# IoT_modules_atmega328_kinemata_v1.net
KiCad netlist of a schematic drawn in EAGLE
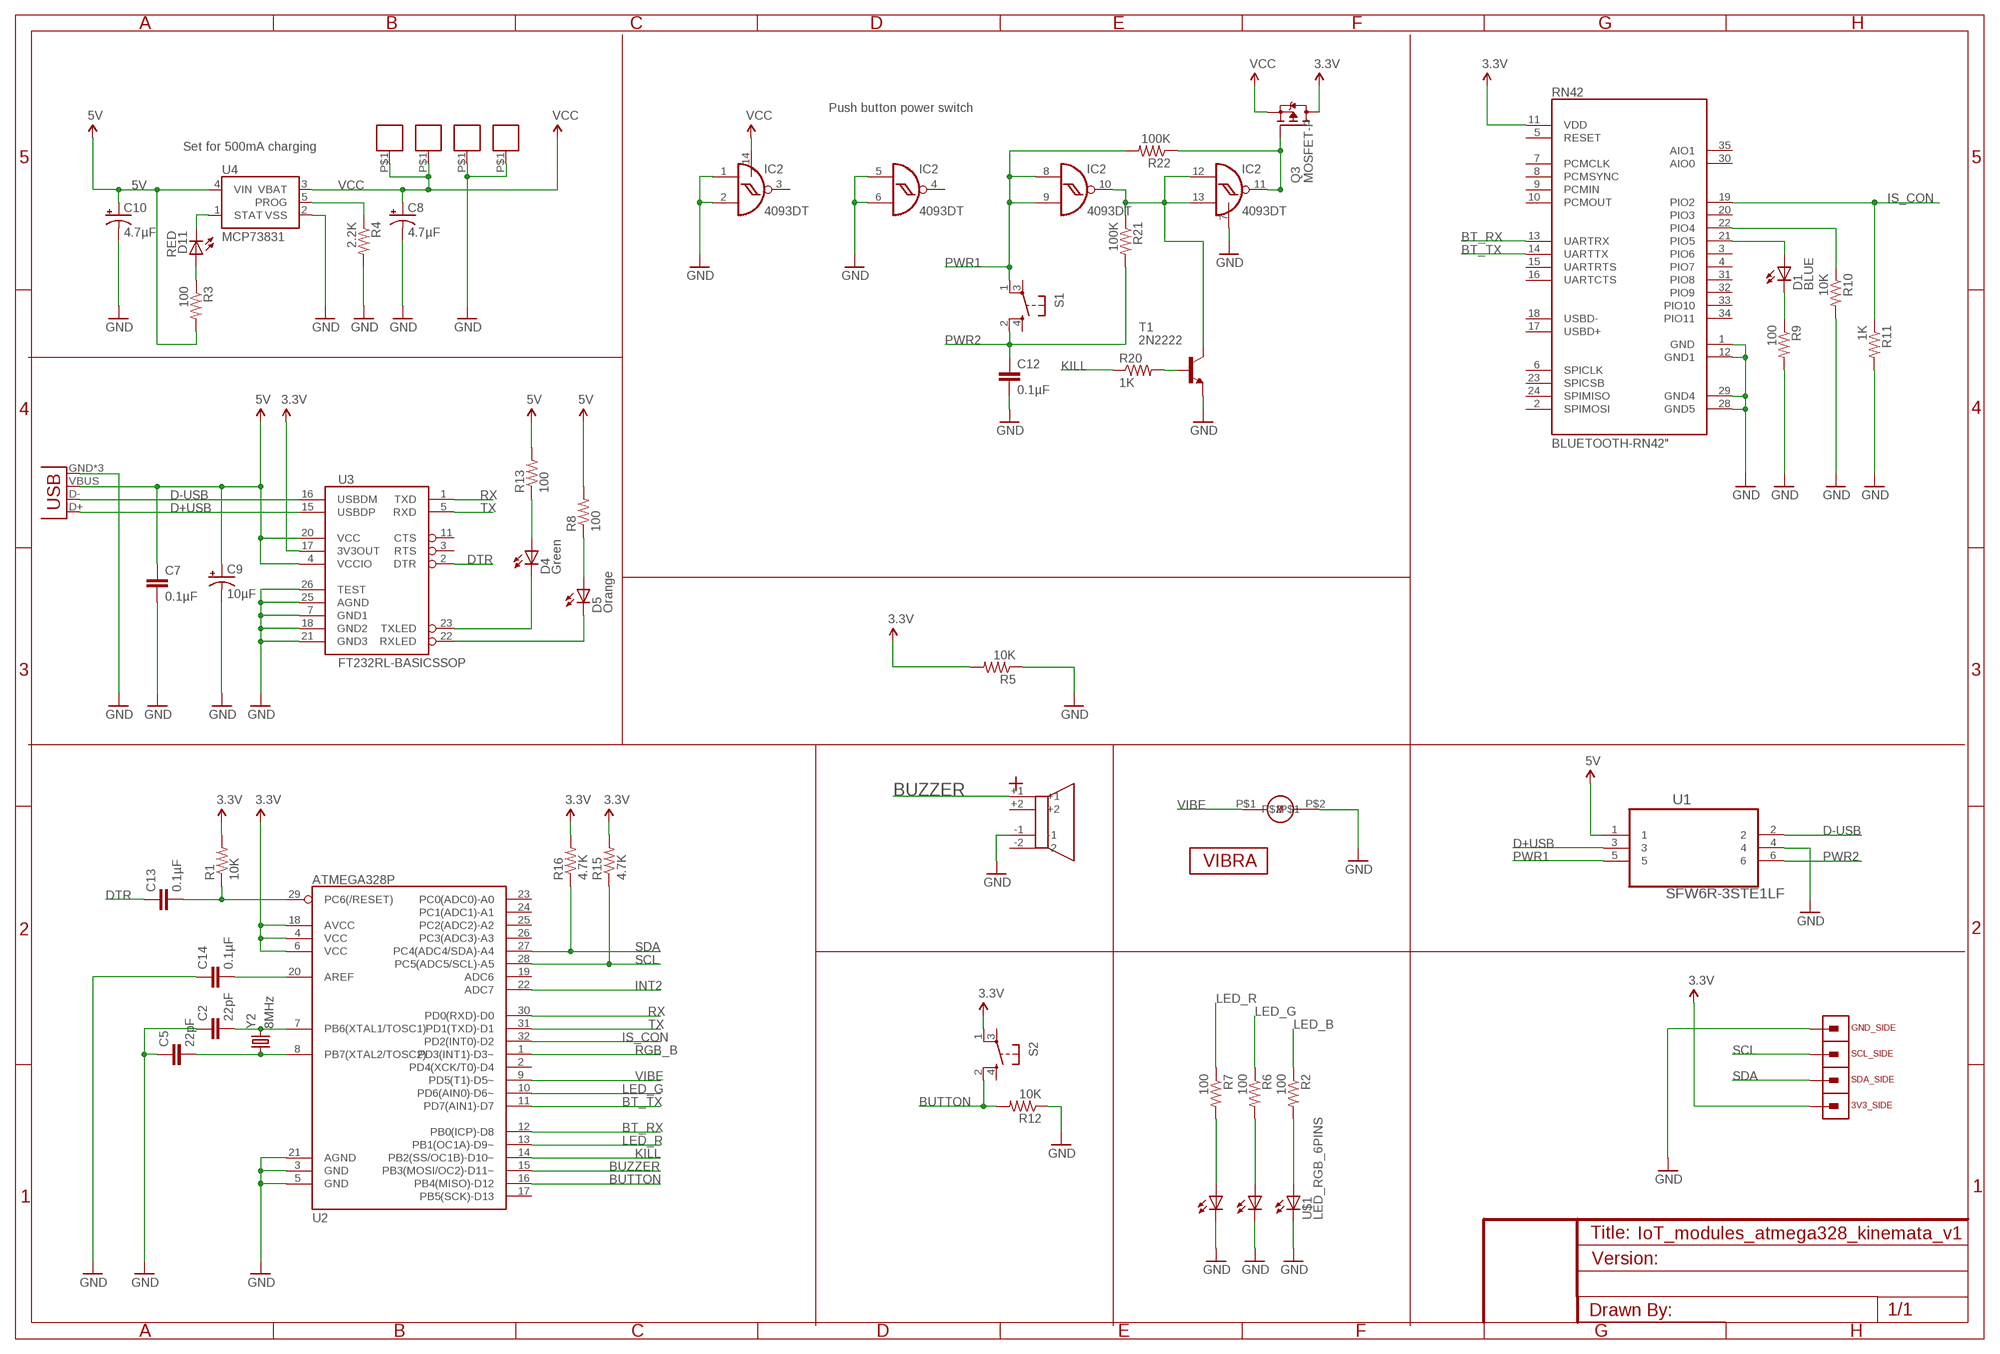
[diagram p0: schematic, sheet 1]

(export (version "E")
  (design (tool "Eeschema 10.0.6"))
  (components
    (comp (ref "3V3_SIDE")
      (value "HEADER_1PIN_MALE")
      (footprint "eagle-import:SPRING_LOADED_HEADER_ANGLE_829-22-020-20-002101_DIGIKEY_ED1320-ND")
      (libsource (lib "eagle-import") (part "HEADER_1PIN_MALE"))
    )
    (comp (ref "BAT+1")
      (value "LIPO_PAD")
      (footprint "eagle-import:LIPO_PAD")
      (libsource (lib "eagle-import") (part "LIPO_PAD"))
    )
    (comp (ref "BAT+2")
      (value "LIPO_PAD")
      (footprint "eagle-import:LIPO_PAD")
      (libsource (lib "eagle-import") (part "LIPO_PAD"))
    )
    (comp (ref "BAT-1")
      (value "LIPO_PAD")
      (footprint "eagle-import:LIPO_PAD")
      (libsource (lib "eagle-import") (part "LIPO_PAD"))
    )
    (comp (ref "BAT-2")
      (value "LIPO_PAD")
      (footprint "eagle-import:LIPO_PAD")
      (libsource (lib "eagle-import") (part "LIPO_PAD"))
    )
    (comp (ref "C2")
      (value "22pF")
      (footprint "eagle-import:1206")
      (libsource (lib "eagle-import") (part "CAP1206"))
    )
    (comp (ref "C5")
      (value "22pF")
      (footprint "eagle-import:1206")
      (libsource (lib "eagle-import") (part "CAP1206"))
    )
    (comp (ref "C7")
      (value "0.1µF")
      (footprint "eagle-import:1206")
      (libsource (lib "eagle-import") (part "CAP1206"))
    )
    (comp (ref "C8")
      (value "4.7µF")
      (footprint "eagle-import:EIA3216")
      (libsource (lib "eagle-import") (part "CAP_POL1206"))
    )
    (comp (ref "C9")
      (value "10µF")
      (footprint "eagle-import:EIA3216")
      (libsource (lib "eagle-import") (part "CAP_POL1206"))
    )
    (comp (ref "C10")
      (value "4.7µF")
      (footprint "eagle-import:EIA3216")
      (libsource (lib "eagle-import") (part "CAP_POL1206"))
    )
    (comp (ref "C12")
      (value "0.1µF")
      (footprint "eagle-import:1206")
      (libsource (lib "eagle-import") (part "CAP1206"))
    )
    (comp (ref "C13")
      (value "0.1µF")
      (footprint "eagle-import:1206")
      (libsource (lib "eagle-import") (part "CAP1206"))
    )
    (comp (ref "C14")
      (value "0.1µF")
      (footprint "eagle-import:1206")
      (libsource (lib "eagle-import") (part "CAP1206"))
    )
    (comp (ref "D1")
      (value "BLUE")
      (footprint "eagle-import:LED-1206")
      (libsource (lib "eagle-import") (part "LED1206"))
    )
    (comp (ref "D4")
      (value "Green")
      (footprint "eagle-import:LED-1206")
      (libsource (lib "eagle-import") (part "LED1206"))
    )
    (comp (ref "D5")
      (value "Orange")
      (footprint "eagle-import:LED-1206")
      (libsource (lib "eagle-import") (part "LED1206"))
    )
    (comp (ref "D11")
      (value "RED")
      (footprint "eagle-import:LED-1206")
      (libsource (lib "eagle-import") (part "LED1206"))
    )
    (comp (ref "GND_SIDE")
      (value "HEADER_1PIN_MALE")
      (footprint "eagle-import:SPRING_LOADED_HEADER_ANGLE_829-22-020-20-002101_DIGIKEY_ED1320-ND")
      (libsource (lib "eagle-import") (part "HEADER_1PIN_MALE"))
    )
    (comp (ref "IC2")
      (value "4093DT")
      (footprint "eagle-import:MC14093B-TSSOP14")
      (libsource (lib "eagle-import") (part "4093DT"))
    )
    (comp (ref "JP6")
      (value "USB-MICROB")
      (footprint "eagle-import:USB-MICROB")
      (libsource (lib "eagle-import") (part "USB-MICROB"))
    )
    (comp (ref "Q3")
      (value "MOSFET-P")
      (footprint "eagle-import:SOT23")
      (libsource (lib "eagle-import") (part "MOSFET-P"))
    )
    (comp (ref "R1")
      (value "10K")
      (footprint "eagle-import:1206")
      (libsource (lib "eagle-import") (part "RESISTOR1206"))
    )
    (comp (ref "R2")
      (value "100")
      (footprint "eagle-import:1206")
      (libsource (lib "eagle-import") (part "RESISTOR1206"))
    )
    (comp (ref "R3")
      (value "100")
      (footprint "eagle-import:1206")
      (libsource (lib "eagle-import") (part "RESISTOR1206"))
    )
    (comp (ref "R4")
      (value "2.2K")
      (footprint "eagle-import:1206")
      (libsource (lib "eagle-import") (part "RESISTOR1206"))
    )
    (comp (ref "R5")
      (value "10K")
      (footprint "eagle-import:1206")
      (libsource (lib "eagle-import") (part "RESISTOR1206"))
    )
    (comp (ref "R6")
      (value "100")
      (footprint "eagle-import:1206")
      (libsource (lib "eagle-import") (part "RESISTOR1206"))
    )
    (comp (ref "R7")
      (value "100")
      (footprint "eagle-import:1206")
      (libsource (lib "eagle-import") (part "RESISTOR1206"))
    )
    (comp (ref "R8")
      (value "100")
      (footprint "eagle-import:1206")
      (libsource (lib "eagle-import") (part "RESISTOR1206"))
    )
    (comp (ref "R9")
      (value "100")
      (footprint "eagle-import:1206")
      (libsource (lib "eagle-import") (part "RESISTOR1206"))
    )
    (comp (ref "R10")
      (value "10K")
      (footprint "eagle-import:1206")
      (libsource (lib "eagle-import") (part "RESISTOR1206"))
    )
    (comp (ref "R11")
      (value "1K")
      (footprint "eagle-import:1206")
      (libsource (lib "eagle-import") (part "RESISTOR1206"))
    )
    (comp (ref "R12")
      (value "10K")
      (footprint "eagle-import:1206")
      (libsource (lib "eagle-import") (part "RESISTOR1206"))
    )
    (comp (ref "R13")
      (value "100")
      (footprint "eagle-import:1206")
      (libsource (lib "eagle-import") (part "RESISTOR1206"))
    )
    (comp (ref "R15")
      (value "4.7K")
      (footprint "eagle-import:1206")
      (libsource (lib "eagle-import") (part "RESISTOR1206"))
    )
    (comp (ref "R16")
      (value "4.7K")
      (footprint "eagle-import:1206")
      (libsource (lib "eagle-import") (part "RESISTOR1206"))
    )
    (comp (ref "R20")
      (value "1K")
      (footprint "eagle-import:1206")
      (libsource (lib "eagle-import") (part "RESISTOR1206"))
    )
    (comp (ref "R21")
      (value "100K")
      (footprint "eagle-import:1206")
      (libsource (lib "eagle-import") (part "RESISTOR1206"))
    )
    (comp (ref "R22")
      (value "100K")
      (footprint "eagle-import:1206")
      (libsource (lib "eagle-import") (part "RESISTOR1206"))
    )
    (comp (ref "RN42")
      (value "BLUETOOTH-RN42\"")
      (footprint "eagle-import:RN42")
      (libsource (lib "eagle-import") (part "BLUETOOTH-RN42{dblquote}"))
    )
    (comp (ref "S1")
      (value "TAC_SWITCH_SIDEWAY")
      (footprint "eagle-import:TACTILE_SWITCH_ANGLE_SMD")
      (libsource (lib "eagle-import") (part "TAC_SWITCH_SIDEWAY"))
    )
    (comp (ref "S2")
      (value "TAC_SWITCH_SIDEWAY")
      (footprint "eagle-import:TACTILE_SWITCH_ANGLE_SMD")
      (libsource (lib "eagle-import") (part "TAC_SWITCH_SIDEWAY"))
    )
    (comp (ref "SCL_SIDE")
      (value "HEADER_1PIN_MALE")
      (footprint "eagle-import:SPRING_LOADED_HEADER_ANGLE_829-22-020-20-002101_DIGIKEY_ED1320-ND")
      (libsource (lib "eagle-import") (part "HEADER_1PIN_MALE"))
    )
    (comp (ref "SDA_SIDE")
      (value "HEADER_1PIN_MALE")
      (footprint "eagle-import:SPRING_LOADED_HEADER_ANGLE_829-22-020-20-002101_DIGIKEY_ED1320-ND")
      (libsource (lib "eagle-import") (part "HEADER_1PIN_MALE"))
    )
    (comp (ref "T1")
      (value "2N2222")
      (footprint "eagle-import:TO92-EBC-OVAL")
      (libsource (lib "eagle-import") (part "2N2222"))
    )
    (comp (ref "U$1")
      (value "LED_RGB_6PINS")
      (footprint "eagle-import:LED_RGB_6PINS")
      (libsource (lib "eagle-import") (part "LED_RGB_6PINS"))
    )
    (comp (ref "U$3")
      (value "BUZZER_4PINS")
      (footprint "eagle-import:FARNELL_BUZZER_MAGNETIC_SMD_3V_2215091")
      (libsource (lib "eagle-import") (part "BUZZER_4PINS"))
    )
    (comp (ref "U$4")
      (value "VIBRATION_MOTOR_SHAPE")
      (footprint "eagle-import:VIBRATION_MOTOR_SHAPE")
      (libsource (lib "eagle-import") (part "VIBRATION_MOTOR_SHAPE"))
    )
    (comp (ref "U$5")
      (value "VIBRATION_MOTOR")
      (footprint "eagle-import:VIBRATION_MOTOR_CABLE")
      (libsource (lib "eagle-import") (part "VIBRATION_MOTOR"))
    )
    (comp (ref "U1")
      (value "SFW6R-3STE1LF")
      (footprint "eagle-import:FCI_SFW6R-3STE1LF")
      (libsource (lib "eagle-import") (part "SFW6R-3STE1LF"))
    )
    (comp (ref "U2")
      (value "ATMEGA328P")
      (footprint "eagle-import:TQFP32-08")
      (libsource (lib "eagle-import") (part "ATMEGA328_SMT"))
    )
    (comp (ref "U3")
      (value "FT232RL-BASICSSOP")
      (footprint "eagle-import:SSOP28DB")
      (libsource (lib "eagle-import") (part "FT232RL-BASICSSOP"))
    )
    (comp (ref "U4")
      (value "MCP73831")
      (footprint "eagle-import:SOT23-5")
      (libsource (lib "eagle-import") (part "MCP73831"))
    )
    (comp (ref "Y2")
      (value "8MHz")
      (footprint "eagle-import:CRYSTAL_8MHZ_SMD_FARNELL_2101329")
      (libsource (lib "eagle-import") (part "CRYSTAL_2PINS5X3.2"))
    )
  )
  (nets
    (net (code "1") (name "/BT_RX") (class "Default")
      (node (ref "RN42") (pin "13") (pinfunction "UARTRX_13") (pintype "bidirectional"))
      (node (ref "U2") (pin "12") (pinfunction "PB0(ICP)-D8_12") (pintype "bidirectional"))
    )
    (net (code "2") (name "/BT_TX") (class "Default")
      (node (ref "RN42") (pin "14") (pinfunction "UARTTX_14") (pintype "bidirectional"))
      (node (ref "U2") (pin "11") (pinfunction "PD7(AIN1)-D7_11") (pintype "bidirectional"))
    )
    (net (code "3") (name "/BUTTON") (class "Default")
      (node (ref "R12") (pin "2") (pinfunction "2_2") (pintype "passive"))
      (node (ref "S2") (pin "2") (pinfunction "B2_2") (pintype "passive"))
      (node (ref "U2") (pin "16") (pinfunction "PB4(MISO)-D12_16") (pintype "bidirectional"))
    )
    (net (code "4") (name "/BUZZER") (class "Default")
      (node (ref "U$3") (pin "+1") (pinfunction "+1_+1") (pintype "bidirectional"))
      (node (ref "U2") (pin "15") (pinfunction "PB3(MOSI/OC2)-D11~{}_15") (pintype "bidirectional"))
    )
    (net (code "5") (name "/D+USB") (class "Default")
      (node (ref "JP6") (pin "D+") (pinfunction "D+_D+") (pintype "bidirectional"))
      (node (ref "U1") (pin "3") (pinfunction "3_3") (pintype "passive"))
      (node (ref "U3") (pin "15") (pinfunction "USBDP_15") (pintype "bidirectional"))
    )
    (net (code "6") (name "/D-USB") (class "Default")
      (node (ref "JP6") (pin "D-") (pinfunction "D-_D-") (pintype "bidirectional"))
      (node (ref "U1") (pin "2") (pinfunction "2_2") (pintype "passive"))
      (node (ref "U3") (pin "16") (pinfunction "USBDM_16") (pintype "bidirectional"))
    )
    (net (code "7") (name "/DTR") (class "Default")
      (node (ref "C13") (pin "1") (pinfunction "1_1") (pintype "passive"))
      (node (ref "U3") (pin "2") (pinfunction "DTR_2") (pintype "bidirectional"))
    )
    (net (code "8") (name "/INT2") (class "Default")
      (node (ref "U2") (pin "22") (pinfunction "ADC7_22") (pintype "bidirectional"))
    )
    (net (code "9") (name "/IS_CON") (class "Default")
      (node (ref "R11") (pin "1") (pinfunction "1_1") (pintype "passive"))
      (node (ref "RN42") (pin "19") (pinfunction "PIO2_19") (pintype "bidirectional"))
      (node (ref "U2") (pin "32") (pinfunction "PD2(INT0)-D2_32") (pintype "bidirectional"))
    )
    (net (code "10") (name "/KILL") (class "Default")
      (node (ref "R20") (pin "1") (pinfunction "1_1") (pintype "passive"))
      (node (ref "U2") (pin "14") (pinfunction "PB2(SS/OC1B)-D10~{}_14") (pintype "bidirectional"))
    )
    (net (code "11") (name "/LED_B") (class "Default")
      (node (ref "R2") (pin "1") (pinfunction "1_1") (pintype "passive"))
    )
    (net (code "12") (name "/LED_G") (class "Default")
      (node (ref "R6") (pin "1") (pinfunction "1_1") (pintype "passive"))
      (node (ref "U2") (pin "10") (pinfunction "PD6(AIN0)-D6~{}_10") (pintype "bidirectional"))
    )
    (net (code "13") (name "/LED_R") (class "Default")
      (node (ref "R7") (pin "1") (pinfunction "1_1") (pintype "passive"))
      (node (ref "U2") (pin "13") (pinfunction "PB1(OC1A)-D9~{}_13") (pintype "bidirectional"))
    )
    (net (code "14") (name "/PWR1") (class "Default")
      (node (ref "IC2") (pin "8") (pinfunction "8_8") (pintype "input"))
      (node (ref "IC2") (pin "9") (pinfunction "9_9") (pintype "input"))
      (node (ref "R22") (pin "2") (pinfunction "2_2") (pintype "passive"))
      (node (ref "S1") (pin "1") (pinfunction "A2_1") (pintype "passive"))
      (node (ref "U1") (pin "5") (pinfunction "5_5") (pintype "passive"))
    )
    (net (code "15") (name "/PWR2") (class "Default")
      (node (ref "C12") (pin "1") (pinfunction "1_1") (pintype "passive"))
      (node (ref "R21") (pin "2") (pinfunction "2_2") (pintype "passive"))
      (node (ref "S1") (pin "2") (pinfunction "B2_2") (pintype "passive"))
      (node (ref "U1") (pin "6") (pinfunction "6_6") (pintype "passive"))
    )
    (net (code "16") (name "/RGB_B") (class "Default")
      (node (ref "U2") (pin "1") (pinfunction "PD3(INT1)-D3~{}_1") (pintype "bidirectional"))
    )
    (net (code "17") (name "/RX") (class "Default")
      (node (ref "U2") (pin "30") (pinfunction "PD0(RXD)-D0_30") (pintype "bidirectional"))
      (node (ref "U3") (pin "1") (pinfunction "TXD_1") (pintype "output"))
    )
    (net (code "18") (name "/SCL") (class "Default")
      (node (ref "R15") (pin "1") (pinfunction "1_1") (pintype "passive"))
      (node (ref "SCL_SIDE") (pin "P$1") (pinfunction "1_P$1") (pintype "bidirectional"))
      (node (ref "U2") (pin "28") (pinfunction "PC5(ADC5/SCL)-A5_28") (pintype "bidirectional"))
    )
    (net (code "19") (name "/SDA") (class "Default")
      (node (ref "R16") (pin "1") (pinfunction "1_1") (pintype "passive"))
      (node (ref "SDA_SIDE") (pin "P$1") (pinfunction "1_P$1") (pintype "bidirectional"))
      (node (ref "U2") (pin "27") (pinfunction "PC4(ADC4/SDA)-A4_27") (pintype "bidirectional"))
    )
    (net (code "20") (name "/TX") (class "Default")
      (node (ref "U2") (pin "31") (pinfunction "PD1(TXD)-D1_31") (pintype "bidirectional"))
      (node (ref "U3") (pin "5") (pinfunction "RXD_5") (pintype "input"))
    )
    (net (code "21") (name "/VIBE") (class "Default")
      (node (ref "U$5") (pin "P$1") (pinfunction "P$1_P$1") (pintype "bidirectional"))
      (node (ref "U2") (pin "9") (pinfunction "PD5(T1)-D5~{}_9") (pintype "bidirectional"))
    )
    (net (code "22") (name "3.3V") (class "Default")
      (node (ref "3V3_SIDE") (pin "P$1") (pinfunction "1_P$1") (pintype "bidirectional"))
      (node (ref "Q3") (pin "3") (pinfunction "D_3") (pintype "passive"))
      (node (ref "R1") (pin "2") (pinfunction "2_2") (pintype "passive"))
      (node (ref "R15") (pin "2") (pinfunction "2_2") (pintype "passive"))
      (node (ref "R16") (pin "2") (pinfunction "2_2") (pintype "passive"))
      (node (ref "R5") (pin "2") (pinfunction "2_2") (pintype "passive"))
      (node (ref "RN42") (pin "11") (pinfunction "VDD_11") (pintype "bidirectional"))
      (node (ref "S2") (pin "1") (pinfunction "A2_1") (pintype "passive"))
      (node (ref "U2") (pin "18") (pinfunction "AVCC_18") (pintype "bidirectional"))
      (node (ref "U2") (pin "4") (pinfunction "VCC_4") (pintype "bidirectional"))
      (node (ref "U2") (pin "6") (pinfunction "VCC_6") (pintype "bidirectional"))
      (node (ref "U3") (pin "17") (pinfunction "3V3OUT_17") (pintype "output"))
    )
    (net (code "23") (name "5V") (class "Default")
      (node (ref "C10") (pin "A") (pinfunction "+_A") (pintype "passive"))
      (node (ref "C7") (pin "1") (pinfunction "1_1") (pintype "passive"))
      (node (ref "C9") (pin "A") (pinfunction "+_A") (pintype "passive"))
      (node (ref "JP6") (pin "VBUS") (pinfunction "VBUS_VBUS") (pintype "bidirectional"))
      (node (ref "R13") (pin "2") (pinfunction "2_2") (pintype "passive"))
      (node (ref "R3") (pin "2") (pinfunction "2_2") (pintype "passive"))
      (node (ref "R8") (pin "2") (pinfunction "2_2") (pintype "passive"))
      (node (ref "U1") (pin "1") (pinfunction "1_1") (pintype "passive"))
      (node (ref "U3") (pin "20") (pinfunction "VCC_20") (pintype "power_in"))
      (node (ref "U3") (pin "4") (pinfunction "VCCIO_4") (pintype "power_in"))
      (node (ref "U4") (pin "4") (pinfunction "VIN_4") (pintype "power_in"))
    )
    (net (code "24") (name "GND") (class "Default")
      (node (ref "BAT-1") (pin "P$1") (pinfunction "P$1_P$1") (pintype "power_in"))
      (node (ref "BAT-2") (pin "P$1") (pinfunction "P$1_P$1") (pintype "power_in"))
      (node (ref "C10") (pin "C") (pinfunction "-_C") (pintype "passive"))
      (node (ref "C12") (pin "2") (pinfunction "2_2") (pintype "passive"))
      (node (ref "C14") (pin "1") (pinfunction "1_1") (pintype "passive"))
      (node (ref "C2") (pin "1") (pinfunction "1_1") (pintype "passive"))
      (node (ref "C5") (pin "1") (pinfunction "1_1") (pintype "passive"))
      (node (ref "C7") (pin "2") (pinfunction "2_2") (pintype "passive"))
      (node (ref "C8") (pin "C") (pinfunction "-_C") (pintype "passive"))
      (node (ref "C9") (pin "C") (pinfunction "-_C") (pintype "passive"))
      (node (ref "GND_SIDE") (pin "P$1") (pinfunction "1_P$1") (pintype "bidirectional"))
      (node (ref "IC2") (pin "1") (pinfunction "1_1") (pintype "input"))
      (node (ref "IC2") (pin "2") (pinfunction "2_2") (pintype "input"))
      (node (ref "IC2") (pin "5") (pinfunction "5_5") (pintype "input"))
      (node (ref "IC2") (pin "6") (pinfunction "6_6") (pintype "input"))
      (node (ref "IC2") (pin "7") (pinfunction "7_7") (pintype "power_in"))
      (node (ref "JP6") (pin "GND") (pinfunction "GND_GND") (pintype "bidirectional"))
      (node (ref "JP6") (pin "MT1") (pinfunction "GND_MT1") (pintype "bidirectional"))
      (node (ref "JP6") (pin "MT2") (pinfunction "GND_MT2") (pintype "bidirectional"))
      (node (ref "R10") (pin "2") (pinfunction "2_2") (pintype "passive"))
      (node (ref "R11") (pin "2") (pinfunction "2_2") (pintype "passive"))
      (node (ref "R12") (pin "1") (pinfunction "1_1") (pintype "passive"))
      (node (ref "R4") (pin "2") (pinfunction "2_2") (pintype "passive"))
      (node (ref "R5") (pin "1") (pinfunction "1_1") (pintype "passive"))
      (node (ref "R9") (pin "2") (pinfunction "2_2") (pintype "passive"))
      (node (ref "RN42") (pin "1") (pinfunction "GND_1") (pintype "bidirectional"))
      (node (ref "RN42") (pin "12") (pinfunction "GND1_12") (pintype "bidirectional"))
      (node (ref "RN42") (pin "28") (pinfunction "GND5_28") (pintype "bidirectional"))
      (node (ref "RN42") (pin "29") (pinfunction "GND4_29") (pintype "bidirectional"))
      (node (ref "T1") (pin "E") (pinfunction "E_E") (pintype "passive"))
      (node (ref "U$1") (pin "BC") (pinfunction "BC_BC") (pintype "passive"))
      (node (ref "U$1") (pin "GC") (pinfunction "GC_GC") (pintype "passive"))
      (node (ref "U$1") (pin "RC") (pinfunction "RC_RC") (pintype "passive"))
      (node (ref "U$3") (pin "-1") (pinfunction "-1_-1") (pintype "bidirectional"))
      (node (ref "U$5") (pin "P$2") (pinfunction "P$2_P$2") (pintype "bidirectional"))
      (node (ref "U1") (pin "4") (pinfunction "4_4") (pintype "passive"))
      (node (ref "U2") (pin "21") (pinfunction "AGND_21") (pintype "bidirectional"))
      (node (ref "U2") (pin "3") (pinfunction "GND_3") (pintype "bidirectional"))
      (node (ref "U2") (pin "5") (pinfunction "GND_5") (pintype "bidirectional"))
      (node (ref "U3") (pin "18") (pinfunction "GND2_18") (pintype "power_in"))
      (node (ref "U3") (pin "21") (pinfunction "GND3_21") (pintype "power_in"))
      (node (ref "U3") (pin "25") (pinfunction "AGND_25") (pintype "power_in"))
      (node (ref "U3") (pin "26") (pinfunction "TEST_26") (pintype "input"))
      (node (ref "U3") (pin "7") (pinfunction "GND1_7") (pintype "power_in"))
      (node (ref "U4") (pin "2") (pinfunction "VSS_2") (pintype "power_in"))
    )
    (net (code "25") (name "Net-(D1-PadC)") (class "Default")
      (node (ref "D1") (pin "C") (pinfunction "C_C") (pintype "passive"))
      (node (ref "R9") (pin "1") (pinfunction "1_1") (pintype "passive"))
    )
    (net (code "26") (name "Net-(D4-PadA)") (class "Default")
      (node (ref "D4") (pin "A") (pinfunction "A_A") (pintype "passive"))
      (node (ref "R13") (pin "1") (pinfunction "1_1") (pintype "passive"))
    )
    (net (code "27") (name "Net-(D5-PadA)") (class "Default")
      (node (ref "D5") (pin "A") (pinfunction "A_A") (pintype "passive"))
      (node (ref "R8") (pin "1") (pinfunction "1_1") (pintype "passive"))
    )
    (net (code "28") (name "Net-(D11-PadA)") (class "Default")
      (node (ref "D11") (pin "A") (pinfunction "A_A") (pintype "passive"))
      (node (ref "R3") (pin "1") (pinfunction "1_1") (pintype "passive"))
    )
    (net (code "29") (name "Net-(IC2-Pad10)") (class "Default")
      (node (ref "IC2") (pin "10") (pinfunction "10_10") (pintype "output"))
      (node (ref "IC2") (pin "12") (pinfunction "12_12") (pintype "input"))
      (node (ref "IC2") (pin "13") (pinfunction "13_13") (pintype "input"))
      (node (ref "R21") (pin "1") (pinfunction "1_1") (pintype "passive"))
      (node (ref "T1") (pin "C") (pinfunction "C_C") (pintype "passive"))
    )
    (net (code "30") (name "Net-(Q3-G)") (class "Default")
      (node (ref "IC2") (pin "11") (pinfunction "11_11") (pintype "output"))
      (node (ref "Q3") (pin "1") (pinfunction "G_1") (pintype "passive"))
      (node (ref "R22") (pin "1") (pinfunction "1_1") (pintype "passive"))
    )
    (net (code "31") (name "Net-(R2-Pad2)") (class "Default")
      (node (ref "R2") (pin "2") (pinfunction "2_2") (pintype "passive"))
      (node (ref "U$1") (pin "GA") (pinfunction "GA_GA") (pintype "passive"))
    )
    (net (code "32") (name "Net-(R6-Pad2)") (class "Default")
      (node (ref "R6") (pin "2") (pinfunction "2_2") (pintype "passive"))
      (node (ref "U$1") (pin "RA") (pinfunction "RA_RA") (pintype "passive"))
    )
    (net (code "33") (name "Net-(R7-Pad2)") (class "Default")
      (node (ref "R7") (pin "2") (pinfunction "2_2") (pintype "passive"))
      (node (ref "U$1") (pin "BA") (pinfunction "BA_BA") (pintype "passive"))
    )
    (net (code "34") (name "Net-(R20-Pad2)") (class "Default")
      (node (ref "R20") (pin "2") (pinfunction "2_2") (pintype "passive"))
      (node (ref "T1") (pin "B") (pinfunction "B_B") (pintype "passive"))
    )
    (net (code "35") (name "Net-(RN42-PIO4)") (class "Default")
      (node (ref "R10") (pin "1") (pinfunction "1_1") (pintype "passive"))
      (node (ref "RN42") (pin "22") (pinfunction "PIO4_22") (pintype "bidirectional"))
    )
    (net (code "36") (name "Net-(RN42-PIO5)") (class "Default")
      (node (ref "D1") (pin "A") (pinfunction "A_A") (pintype "passive"))
      (node (ref "RN42") (pin "21") (pinfunction "PIO5_21") (pintype "bidirectional"))
    )
    (net (code "37") (name "Net-(U2-AREF)") (class "Default")
      (node (ref "C14") (pin "2") (pinfunction "2_2") (pintype "passive"))
      (node (ref "U2") (pin "20") (pinfunction "AREF_20") (pintype "bidirectional"))
    )
    (net (code "38") (name "Net-(U2-PB6(XTAL1{slash}TOSC1))") (class "Default")
      (node (ref "C2") (pin "2") (pinfunction "2_2") (pintype "passive"))
      (node (ref "U2") (pin "7") (pinfunction "PB6(XTAL1/TOSC1)_7") (pintype "bidirectional"))
      (node (ref "Y2") (pin "P$2") (pinfunction "2_P$2") (pintype "passive"))
    )
    (net (code "39") (name "Net-(U2-PB7(XTAL2{slash}TOSC2))") (class "Default")
      (node (ref "C5") (pin "2") (pinfunction "2_2") (pintype "passive"))
      (node (ref "U2") (pin "8") (pinfunction "PB7(XTAL2/TOSC2)_8") (pintype "bidirectional"))
      (node (ref "Y2") (pin "P$1") (pinfunction "1_P$1") (pintype "passive"))
    )
    (net (code "40") (name "Net-(U2-PC6({slash}RESET))") (class "Default")
      (node (ref "C13") (pin "2") (pinfunction "2_2") (pintype "passive"))
      (node (ref "R1") (pin "1") (pinfunction "1_1") (pintype "passive"))
      (node (ref "U2") (pin "29") (pinfunction "PC6(/RESET)_29") (pintype "bidirectional"))
    )
    (net (code "41") (name "Net-(U3-RXLED)") (class "Default")
      (node (ref "D5") (pin "C") (pinfunction "C_C") (pintype "passive"))
      (node (ref "U3") (pin "22") (pinfunction "RXLED_22") (pintype "bidirectional"))
    )
    (net (code "42") (name "Net-(U3-TXLED)") (class "Default")
      (node (ref "D4") (pin "C") (pinfunction "C_C") (pintype "passive"))
      (node (ref "U3") (pin "23") (pinfunction "TXLED_23") (pintype "bidirectional"))
    )
    (net (code "43") (name "Net-(U4-PROG)") (class "Default")
      (node (ref "R4") (pin "1") (pinfunction "1_1") (pintype "passive"))
      (node (ref "U4") (pin "5") (pinfunction "PROG_5") (pintype "input"))
    )
    (net (code "44") (name "Net-(U4-STAT)") (class "Default")
      (node (ref "D11") (pin "C") (pinfunction "C_C") (pintype "passive"))
      (node (ref "U4") (pin "1") (pinfunction "STAT_1") (pintype "output"))
    )
    (net (code "45") (name "VCC") (class "Default")
      (node (ref "BAT+1") (pin "P$1") (pinfunction "P$1_P$1") (pintype "power_in"))
      (node (ref "BAT+2") (pin "P$1") (pinfunction "P$1_P$1") (pintype "power_in"))
      (node (ref "C8") (pin "A") (pinfunction "+_A") (pintype "passive"))
      (node (ref "IC2") (pin "14") (pinfunction "14_14") (pintype "power_in"))
      (node (ref "Q3") (pin "2") (pinfunction "S_2") (pintype "passive"))
      (node (ref "U4") (pin "3") (pinfunction "VBAT_3") (pintype "power_in"))
    )
    (net (code "46") (name "unconnected-(IC2-Pad3)") (class "Default")
      (node (ref "IC2") (pin "3") (pinfunction "3_3") (pintype "output"))
    )
    (net (code "47") (name "unconnected-(IC2-Pad4)") (class "Default")
      (node (ref "IC2") (pin "4") (pinfunction "4_4") (pintype "output"))
    )
    (net (code "48") (name "unconnected-(RN42-AIO0-Pad30)") (class "Default")
      (node (ref "RN42") (pin "30") (pinfunction "AIO0_30") (pintype "bidirectional"))
    )
    (net (code "49") (name "unconnected-(RN42-AIO1-Pad35)") (class "Default")
      (node (ref "RN42") (pin "35") (pinfunction "AIO1_35") (pintype "bidirectional"))
    )
    (net (code "50") (name "unconnected-(RN42-PCMCLK-Pad7)") (class "Default")
      (node (ref "RN42") (pin "7") (pinfunction "PCMCLK_7") (pintype "bidirectional"))
    )
    (net (code "51") (name "unconnected-(RN42-PCMIN-Pad9)") (class "Default")
      (node (ref "RN42") (pin "9") (pinfunction "PCMIN_9") (pintype "bidirectional"))
    )
    (net (code "52") (name "unconnected-(RN42-PCMOUT-Pad10)") (class "Default")
      (node (ref "RN42") (pin "10") (pinfunction "PCMOUT_10") (pintype "bidirectional"))
    )
    (net (code "53") (name "unconnected-(RN42-PCMSYNC-Pad8)") (class "Default")
      (node (ref "RN42") (pin "8") (pinfunction "PCMSYNC_8") (pintype "bidirectional"))
    )
    (net (code "54") (name "unconnected-(RN42-PIO3-Pad20)") (class "Default")
      (node (ref "RN42") (pin "20") (pinfunction "PIO3_20") (pintype "bidirectional"))
    )
    (net (code "55") (name "unconnected-(RN42-PIO6-Pad3)") (class "Default")
      (node (ref "RN42") (pin "3") (pinfunction "PIO6_3") (pintype "bidirectional"))
    )
    (net (code "56") (name "unconnected-(RN42-PIO7-Pad4)") (class "Default")
      (node (ref "RN42") (pin "4") (pinfunction "PIO7_4") (pintype "bidirectional"))
    )
    (net (code "57") (name "unconnected-(RN42-PIO8-Pad31)") (class "Default")
      (node (ref "RN42") (pin "31") (pinfunction "PIO8_31") (pintype "bidirectional"))
    )
    (net (code "58") (name "unconnected-(RN42-PIO9-Pad32)") (class "Default")
      (node (ref "RN42") (pin "32") (pinfunction "PIO9_32") (pintype "bidirectional"))
    )
    (net (code "59") (name "unconnected-(RN42-PIO10-Pad33)") (class "Default")
      (node (ref "RN42") (pin "33") (pinfunction "PIO10_33") (pintype "bidirectional"))
    )
    (net (code "60") (name "unconnected-(RN42-PIO11-Pad34)") (class "Default")
      (node (ref "RN42") (pin "34") (pinfunction "PIO11_34") (pintype "bidirectional"))
    )
    (net (code "61") (name "unconnected-(RN42-RESET-Pad5)") (class "Default")
      (node (ref "RN42") (pin "5") (pinfunction "RESET_5") (pintype "bidirectional"))
    )
    (net (code "62") (name "unconnected-(RN42-SPICLK-Pad6)") (class "Default")
      (node (ref "RN42") (pin "6") (pinfunction "SPICLK_6") (pintype "bidirectional"))
    )
    (net (code "63") (name "unconnected-(RN42-SPICSB-Pad23)") (class "Default")
      (node (ref "RN42") (pin "23") (pinfunction "SPICSB_23") (pintype "bidirectional"))
    )
    (net (code "64") (name "unconnected-(RN42-SPIMISO-Pad24)") (class "Default")
      (node (ref "RN42") (pin "24") (pinfunction "SPIMISO_24") (pintype "bidirectional"))
    )
    (net (code "65") (name "unconnected-(RN42-SPIMOSI-Pad2)") (class "Default")
      (node (ref "RN42") (pin "2") (pinfunction "SPIMOSI_2") (pintype "bidirectional"))
    )
    (net (code "66") (name "unconnected-(RN42-UARTCTS-Pad16)") (class "Default")
      (node (ref "RN42") (pin "16") (pinfunction "UARTCTS_16") (pintype "bidirectional"))
    )
    (net (code "67") (name "unconnected-(RN42-UARTRTS-Pad15)") (class "Default")
      (node (ref "RN42") (pin "15") (pinfunction "UARTRTS_15") (pintype "bidirectional"))
    )
    (net (code "68") (name "unconnected-(RN42-USBD+-Pad17)") (class "Default")
      (node (ref "RN42") (pin "17") (pinfunction "USBD+_17") (pintype "bidirectional"))
    )
    (net (code "69") (name "unconnected-(RN42-USBD--Pad18)") (class "Default")
      (node (ref "RN42") (pin "18") (pinfunction "USBD-_18") (pintype "bidirectional"))
    )
    (net (code "70") (name "unconnected-(S1-A1-Pad3)") (class "Default")
      (node (ref "S1") (pin "3") (pinfunction "A1_3") (pintype "passive"))
    )
    (net (code "71") (name "unconnected-(S1-B1-Pad4)") (class "Default")
      (node (ref "S1") (pin "4") (pinfunction "B1_4") (pintype "passive"))
    )
    (net (code "72") (name "unconnected-(S2-A1-Pad3)") (class "Default")
      (node (ref "S2") (pin "3") (pinfunction "A1_3") (pintype "passive"))
    )
    (net (code "73") (name "unconnected-(S2-B1-Pad4)") (class "Default")
      (node (ref "S2") (pin "4") (pinfunction "B1_4") (pintype "passive"))
    )
    (net (code "74") (name "unconnected-(U$3-Pad+2)") (class "Default")
      (node (ref "U$3") (pin "+2") (pinfunction "+2_+2") (pintype "bidirectional"))
    )
    (net (code "75") (name "unconnected-(U$3-Pad-2)") (class "Default")
      (node (ref "U$3") (pin "-2") (pinfunction "-2_-2") (pintype "bidirectional"))
    )
    (net (code "76") (name "unconnected-(U2-ADC6-Pad19)") (class "Default")
      (node (ref "U2") (pin "19") (pinfunction "ADC6_19") (pintype "bidirectional"))
    )
    (net (code "77") (name "unconnected-(U2-PB5(SCK)-D13-Pad17)") (class "Default")
      (node (ref "U2") (pin "17") (pinfunction "PB5(SCK)-D13_17") (pintype "bidirectional"))
    )
    (net (code "78") (name "unconnected-(U2-PC0(ADC0)-A0-Pad23)") (class "Default")
      (node (ref "U2") (pin "23") (pinfunction "PC0(ADC0)-A0_23") (pintype "bidirectional"))
    )
    (net (code "79") (name "unconnected-(U2-PC1(ADC1)-A1-Pad24)") (class "Default")
      (node (ref "U2") (pin "24") (pinfunction "PC1(ADC1)-A1_24") (pintype "bidirectional"))
    )
    (net (code "80") (name "unconnected-(U2-PC2(ADC2)-A2-Pad25)") (class "Default")
      (node (ref "U2") (pin "25") (pinfunction "PC2(ADC2)-A2_25") (pintype "bidirectional"))
    )
    (net (code "81") (name "unconnected-(U2-PC3(ADC3)-A3-Pad26)") (class "Default")
      (node (ref "U2") (pin "26") (pinfunction "PC3(ADC3)-A3_26") (pintype "bidirectional"))
    )
    (net (code "82") (name "unconnected-(U2-PD4(XCK{slash}T0)-D4-Pad2)") (class "Default")
      (node (ref "U2") (pin "2") (pinfunction "PD4(XCK/T0)-D4_2") (pintype "bidirectional"))
    )
    (net (code "83") (name "unconnected-(U3-CTS-Pad11)") (class "Default")
      (node (ref "U3") (pin "11") (pinfunction "CTS_11") (pintype "bidirectional"))
    )
    (net (code "84") (name "unconnected-(U3-RTS-Pad3)") (class "Default")
      (node (ref "U3") (pin "3") (pinfunction "RTS_3") (pintype "bidirectional"))
    )
  )
)
